# usb_input.net
KiCad netlist of a schematic drawn in Altium Designer
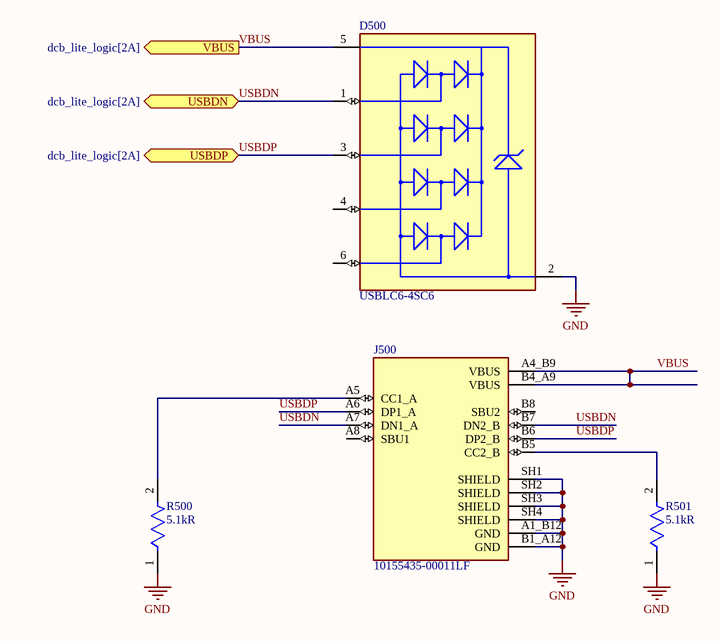
[diagram p0: usb_input.SchDoc]

(export (version "E")
  (design (tool "Eeschema 10.0.6"))
  (components
    (comp (ref "D500")
      (value "USBLC6-4SC6")
      (footprint "FP-SOT23-6L-MFG")
      (description "ESD Suppressor 15KV 6-Pin SOT-23 T/R - Product that comes on tape, but is not reeled")
      (libsource (lib "StackFoundry LLC") (part "3e70b616ccdc4c88b528e1820c4a7da"))
    )
    (comp (ref "J500")
      (value "10155435-00011LF")
      (footprint "AMPHENOL_10155435-00011LF")
      (description "16 Position 5 A USB Right Angle Receptacle Connector")
      (fields (field (name "MF") "Amphenol ICC (FCI)"))
      (libsource (lib "StackFoundry LLC") (part "10155435-00011LF"))
    )
    (comp (ref "R500")
      (value "5.1kR")
      (footprint "FP-AC0402-IPC_A")
      (description "SMD Chip Resistor, 5.1 kOhm, ± 1%, 63 mW, 0402 [1005 Metric], Thick Film, General Purpose")
      (fields (field (name "TOLERANCE") "1%") (field (name "Comment") "AC0402FR-075K1L"))
      (libsource (lib "StackFoundry LLC") (part "1029c3af85768c4190bb7ad29bc67b5"))
    )
    (comp (ref "R501")
      (value "5.1kR")
      (footprint "FP-AC0402-IPC_A")
      (description "SMD Chip Resistor, 5.1 kOhm, ± 1%, 63 mW, 0402 [1005 Metric], Thick Film, General Purpose")
      (fields (field (name "TOLERANCE") "1%") (field (name "Comment") "AC0402FR-075K1L"))
      (libsource (lib "StackFoundry LLC") (part "1029c3af85768c4190bb7ad29bc67b5"))
    )
  )
  (nets
    (net (code "1") (name "/USBDN") (class "Default")
      (node (ref "D500") (pin "1") (pinfunction "I/O1_1") (pintype "bidirectional"))
      (node (ref "J500") (pin "A7") (pinfunction "DN1_A_A7") (pintype "bidirectional"))
      (node (ref "J500") (pin "B7") (pinfunction "DN2_B_B7") (pintype "bidirectional"))
    )
    (net (code "2") (name "/USBDP") (class "Default")
      (node (ref "D500") (pin "3") (pinfunction "I/O2_3") (pintype "bidirectional"))
      (node (ref "J500") (pin "A6") (pinfunction "DP1_A_A6") (pintype "bidirectional"))
      (node (ref "J500") (pin "B6") (pinfunction "DP2_B_B6") (pintype "bidirectional"))
    )
    (net (code "3") (name "/VBUS") (class "Default")
      (node (ref "D500") (pin "5") (pinfunction "VBUS_5") (pintype "power_in"))
      (node (ref "J500") (pin "A4_B9") (pinfunction "VBUS_A4_B9") (pintype "power_in"))
      (node (ref "J500") (pin "B4_A9") (pinfunction "VBUS_B4_A9") (pintype "power_in"))
    )
    (net (code "4") (name "GND") (class "Default")
      (node (ref "D500") (pin "2") (pinfunction "GND_2") (pintype "power_in"))
      (node (ref "J500") (pin "A1_B12") (pinfunction "GND_A1_B12") (pintype "power_in"))
      (node (ref "J500") (pin "B1_A12") (pinfunction "GND_B1_A12") (pintype "power_in"))
      (node (ref "J500") (pin "SH1") (pinfunction "SHIELD_SH1") (pintype "passive"))
      (node (ref "J500") (pin "SH2") (pinfunction "SHIELD_SH2") (pintype "passive"))
      (node (ref "J500") (pin "SH3") (pinfunction "SHIELD_SH3") (pintype "passive"))
      (node (ref "J500") (pin "SH4") (pinfunction "SHIELD_SH4") (pintype "passive"))
      (node (ref "R500") (pin "1") (pinfunction "1_1") (pintype "passive"))
      (node (ref "R501") (pin "1") (pinfunction "1_1") (pintype "passive"))
    )
    (net (code "5") (name "Net-(J500-CC1_A)") (class "Default")
      (node (ref "J500") (pin "A5") (pinfunction "CC1_A_A5") (pintype "bidirectional"))
      (node (ref "R500") (pin "2") (pinfunction "2_2") (pintype "passive"))
    )
    (net (code "6") (name "Net-(J500-CC2_B)") (class "Default")
      (node (ref "J500") (pin "B5") (pinfunction "CC2_B_B5") (pintype "bidirectional"))
      (node (ref "R501") (pin "2") (pinfunction "2_2") (pintype "passive"))
    )
    (net (code "7") (name "unconnected-(D500-I{slash}O3-Pad4)") (class "Default")
      (node (ref "D500") (pin "4") (pinfunction "I/O3_4") (pintype "bidirectional"))
    )
    (net (code "8") (name "unconnected-(D500-I{slash}O4-Pad6)") (class "Default")
      (node (ref "D500") (pin "6") (pinfunction "I/O4_6") (pintype "bidirectional"))
    )
    (net (code "9") (name "unconnected-(J500-SBU1-PadA8)") (class "Default")
      (node (ref "J500") (pin "A8") (pinfunction "SBU1_A8") (pintype "bidirectional"))
    )
    (net (code "10") (name "unconnected-(J500-SBU2-PadB8)") (class "Default")
      (node (ref "J500") (pin "B8") (pinfunction "SBU2_B8") (pintype "bidirectional"))
    )
  )
)
